# keyboard.net
KiCad netlist of a schematic drawn in Altium Designer
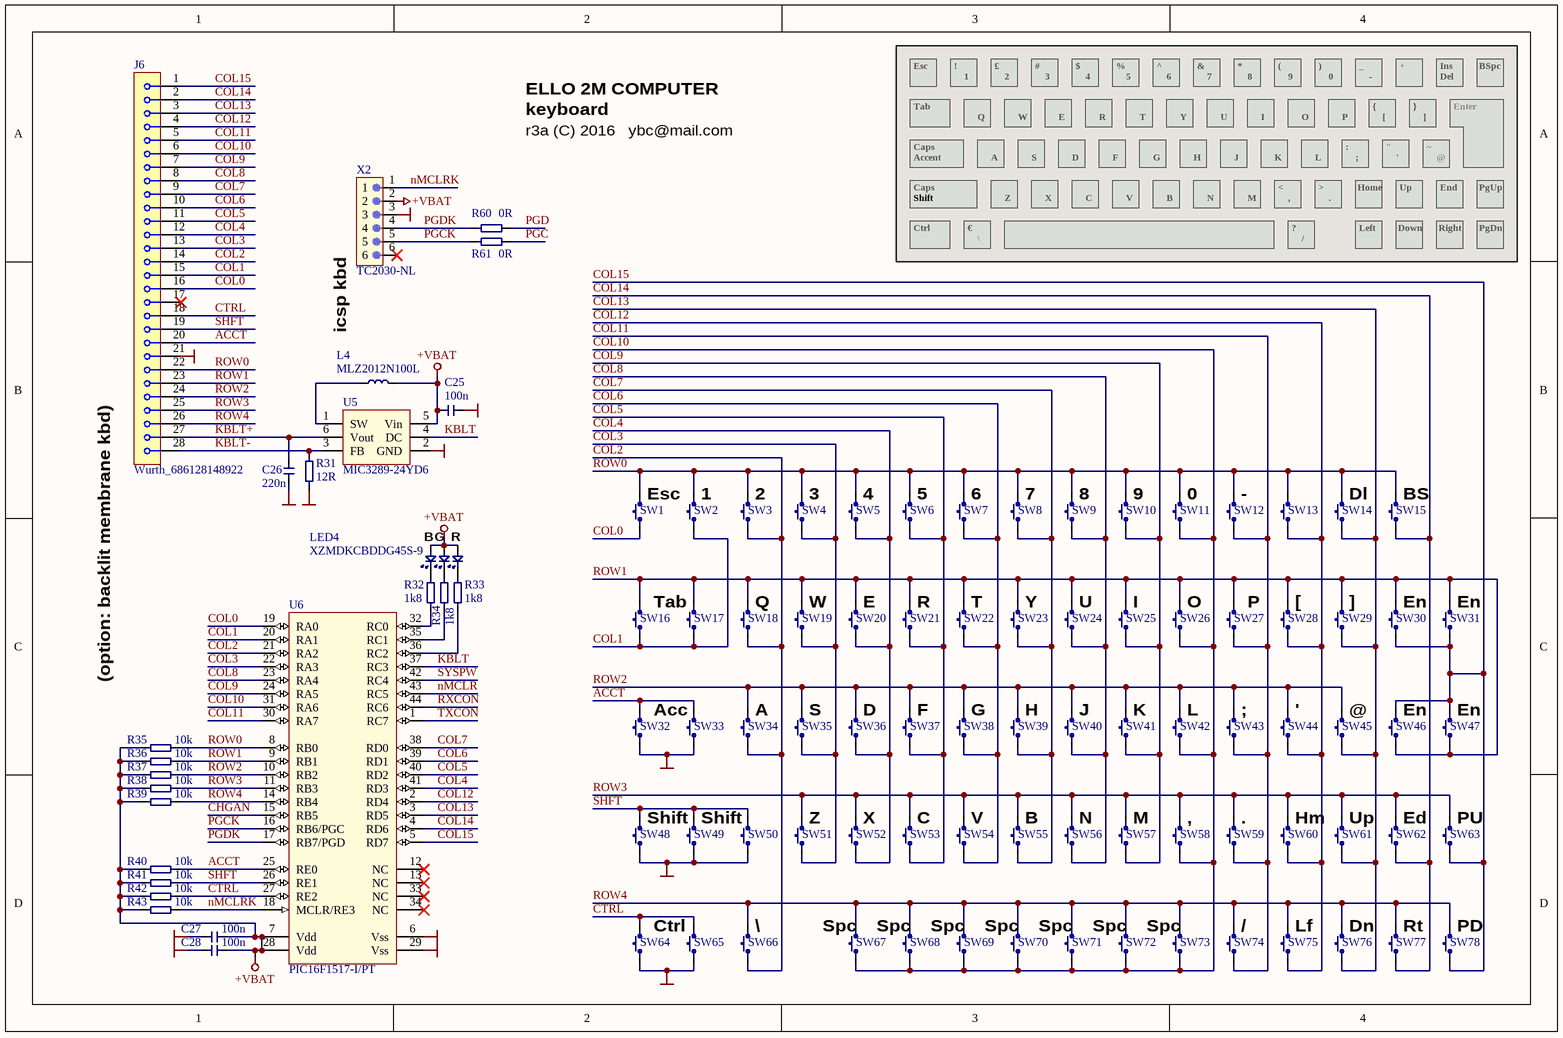
[diagram p0: keyboard.SchDoc]

(export (version "E")
  (design (tool "Eeschema 10.0.6"))
  (components
    (comp (ref "C25")
      (value "100n")
      (footprint "_0603")
      (description "Capacitor")
      (libsource (lib "Discretes") (part "Capacitor"))
    )
    (comp (ref "C26")
      (value "220n")
      (footprint "_0603")
      (description "Capacitor")
      (libsource (lib "Discretes") (part "Capacitor"))
    )
    (comp (ref "C27")
      (value "100n")
      (footprint "_0603")
      (description "Capacitor")
      (libsource (lib "Discretes") (part "Capacitor"))
    )
    (comp (ref "C28")
      (value "100n")
      (footprint "_0603")
      (description "Capacitor")
      (libsource (lib "Discretes") (part "Capacitor"))
    )
    (comp (ref "J6")
      (value "Wurth_686128148922")
      (footprint "Wurth_686128148922")
      (description "Single row, 28-way connector")
      (libsource (lib "Connectors") (part "Connector 1x28"))
    )
    (comp (ref "L4")
      (value "MLZ2012N100L")
      (footprint "_0805_IND")
      (description "Inductor")
      (libsource (lib "Discretes") (part "Inductor"))
    )
    (comp (ref "LED4")
      (value "XZMDKCBDDG45S-9")
      (footprint "LED RGB XZMDKCBDDG45S-9")
      (description "RGB Light Emitting Diode")
      (libsource (lib "Discretes") (part "LED Triple"))
    )
    (comp (ref "R31")
      (value "12R")
      (footprint "_1206")
      (description "Resistor")
      (libsource (lib "") (part "Resistor_2"))
    )
    (comp (ref "R32")
      (value "1k8")
      (footprint "_0603")
      (description "Resistor")
      (libsource (lib "") (part "Resistor_1"))
    )
    (comp (ref "R33")
      (value "1k8")
      (footprint "_0603")
      (description "Resistor")
      (libsource (lib "") (part "Resistor_1"))
    )
    (comp (ref "R34")
      (value "1k8")
      (footprint "_0603")
      (description "Resistor")
      (libsource (lib "") (part "Resistor_1"))
    )
    (comp (ref "R35")
      (value "10k")
      (footprint "_0603")
      (description "Resistor")
      (libsource (lib "Discretes") (part "Resistor"))
    )
    (comp (ref "R36")
      (value "10k")
      (footprint "_0603")
      (description "Resistor")
      (libsource (lib "Discretes") (part "Resistor"))
    )
    (comp (ref "R37")
      (value "10k")
      (footprint "_0603")
      (description "Resistor")
      (libsource (lib "Discretes") (part "Resistor"))
    )
    (comp (ref "R38")
      (value "10k")
      (footprint "_0603")
      (description "Resistor")
      (libsource (lib "Discretes") (part "Resistor"))
    )
    (comp (ref "R39")
      (value "10k")
      (footprint "_0603")
      (description "Resistor")
      (libsource (lib "Discretes") (part "Resistor"))
    )
    (comp (ref "R40")
      (value "10k")
      (footprint "_0603")
      (description "Resistor")
      (libsource (lib "Discretes") (part "Resistor"))
    )
    (comp (ref "R41")
      (value "10k")
      (footprint "_0603")
      (description "Resistor")
      (libsource (lib "Discretes") (part "Resistor"))
    )
    (comp (ref "R42")
      (value "10k")
      (footprint "_0603")
      (description "Resistor")
      (libsource (lib "Discretes") (part "Resistor"))
    )
    (comp (ref "R43")
      (value "10k")
      (footprint "_0603")
      (description "Resistor")
      (libsource (lib "Discretes") (part "Resistor"))
    )
    (comp (ref "R60")
      (value "0R")
      (footprint "_0603")
      (description "Resistor")
      (libsource (lib "") (part "Resistor_3"))
    )
    (comp (ref "R61")
      (value "0R")
      (footprint "_0603")
      (description "Resistor")
      (libsource (lib "") (part "Resistor_3"))
    )
    (comp (ref "SW1")
      (value "~")
      (footprint "Rubber Switch Pad (12mm)")
      (description "Switch, Momentary, Normal Open")
      (libsource (lib "Switches") (part "Switch MNO SPST"))
    )
    (comp (ref "SW2")
      (value "~")
      (footprint "Rubber Switch Pad (12mm)")
      (description "Switch, Momentary, Normal Open")
      (libsource (lib "Switches") (part "Switch MNO SPST"))
    )
    (comp (ref "SW3")
      (value "~")
      (footprint "Rubber Switch Pad (12mm)")
      (description "Switch, Momentary, Normal Open")
      (libsource (lib "Switches") (part "Switch MNO SPST"))
    )
    (comp (ref "SW4")
      (value "~")
      (footprint "Rubber Switch Pad (12mm)")
      (description "Switch, Momentary, Normal Open")
      (libsource (lib "Switches") (part "Switch MNO SPST"))
    )
    (comp (ref "SW5")
      (value "~")
      (footprint "Rubber Switch Pad (12mm)")
      (description "Switch, Momentary, Normal Open")
      (libsource (lib "Switches") (part "Switch MNO SPST"))
    )
    (comp (ref "SW6")
      (value "~")
      (footprint "Rubber Switch Pad (12mm)")
      (description "Switch, Momentary, Normal Open")
      (libsource (lib "Switches") (part "Switch MNO SPST"))
    )
    (comp (ref "SW7")
      (value "~")
      (footprint "Rubber Switch Pad (12mm)")
      (description "Switch, Momentary, Normal Open")
      (libsource (lib "Switches") (part "Switch MNO SPST"))
    )
    (comp (ref "SW8")
      (value "~")
      (footprint "Rubber Switch Pad (12mm)")
      (description "Switch, Momentary, Normal Open")
      (libsource (lib "Switches") (part "Switch MNO SPST"))
    )
    (comp (ref "SW9")
      (value "~")
      (footprint "Rubber Switch Pad (12mm)")
      (description "Switch, Momentary, Normal Open")
      (libsource (lib "Switches") (part "Switch MNO SPST"))
    )
    (comp (ref "SW10")
      (value "~")
      (footprint "Rubber Switch Pad (12mm)")
      (description "Switch, Momentary, Normal Open")
      (libsource (lib "Switches") (part "Switch MNO SPST"))
    )
    (comp (ref "SW11")
      (value "~")
      (footprint "Rubber Switch Pad (12mm)")
      (description "Switch, Momentary, Normal Open")
      (libsource (lib "Switches") (part "Switch MNO SPST"))
    )
    (comp (ref "SW12")
      (value "~")
      (footprint "Rubber Switch Pad (12mm)")
      (description "Switch, Momentary, Normal Open")
      (libsource (lib "Switches") (part "Switch MNO SPST"))
    )
    (comp (ref "SW13")
      (value "~")
      (footprint "Rubber Switch Pad (12mm)")
      (description "Switch, Momentary, Normal Open")
      (libsource (lib "Switches") (part "Switch MNO SPST"))
    )
    (comp (ref "SW14")
      (value "~")
      (footprint "Rubber Switch Pad (12mm)")
      (description "Switch, Momentary, Normal Open")
      (libsource (lib "Switches") (part "Switch MNO SPST"))
    )
    (comp (ref "SW15")
      (value "~")
      (footprint "Rubber Switch Pad (12mm)")
      (description "Switch, Momentary, Normal Open")
      (libsource (lib "Switches") (part "Switch MNO SPST"))
    )
    (comp (ref "SW16")
      (value "~")
      (footprint "Rubber Switch Pad (8x12mm)")
      (description "Switch, Momentary, Normal Open")
      (libsource (lib "Switches") (part "Switch MNO SPST"))
    )
    (comp (ref "SW17")
      (value "~")
      (footprint "Rubber Switch Pad (8x12mm)")
      (description "Switch, Momentary, Normal Open")
      (libsource (lib "Switches") (part "Switch MNO SPST"))
    )
    (comp (ref "SW18")
      (value "~")
      (footprint "Rubber Switch Pad (12mm)")
      (description "Switch, Momentary, Normal Open")
      (libsource (lib "Switches") (part "Switch MNO SPST"))
    )
    (comp (ref "SW19")
      (value "~")
      (footprint "Rubber Switch Pad (12mm)")
      (description "Switch, Momentary, Normal Open")
      (libsource (lib "Switches") (part "Switch MNO SPST"))
    )
    (comp (ref "SW20")
      (value "~")
      (footprint "Rubber Switch Pad (12mm)")
      (description "Switch, Momentary, Normal Open")
      (libsource (lib "Switches") (part "Switch MNO SPST"))
    )
    (comp (ref "SW21")
      (value "~")
      (footprint "Rubber Switch Pad (12mm)")
      (description "Switch, Momentary, Normal Open")
      (libsource (lib "Switches") (part "Switch MNO SPST"))
    )
    (comp (ref "SW22")
      (value "~")
      (footprint "Rubber Switch Pad (12mm)")
      (description "Switch, Momentary, Normal Open")
      (libsource (lib "Switches") (part "Switch MNO SPST"))
    )
    (comp (ref "SW23")
      (value "~")
      (footprint "Rubber Switch Pad (12mm)")
      (description "Switch, Momentary, Normal Open")
      (libsource (lib "Switches") (part "Switch MNO SPST"))
    )
    (comp (ref "SW24")
      (value "~")
      (footprint "Rubber Switch Pad (12mm)")
      (description "Switch, Momentary, Normal Open")
      (libsource (lib "Switches") (part "Switch MNO SPST"))
    )
    (comp (ref "SW25")
      (value "~")
      (footprint "Rubber Switch Pad (12mm)")
      (description "Switch, Momentary, Normal Open")
      (libsource (lib "Switches") (part "Switch MNO SPST"))
    )
    (comp (ref "SW26")
      (value "~")
      (footprint "Rubber Switch Pad (12mm)")
      (description "Switch, Momentary, Normal Open")
      (libsource (lib "Switches") (part "Switch MNO SPST"))
    )
    (comp (ref "SW27")
      (value "~")
      (footprint "Rubber Switch Pad (12mm)")
      (description "Switch, Momentary, Normal Open")
      (libsource (lib "Switches") (part "Switch MNO SPST"))
    )
    (comp (ref "SW28")
      (value "~")
      (footprint "Rubber Switch Pad (12mm)")
      (description "Switch, Momentary, Normal Open")
      (libsource (lib "Switches") (part "Switch MNO SPST"))
    )
    (comp (ref "SW29")
      (value "~")
      (footprint "Rubber Switch Pad (12mm)")
      (description "Switch, Momentary, Normal Open")
      (libsource (lib "Switches") (part "Switch MNO SPST"))
    )
    (comp (ref "SW30")
      (value "~")
      (footprint "Rubber Switch Pad (10x16mm)")
      (description "Switch, Momentary, Normal Open")
      (libsource (lib "Switches") (part "Switch MNO SPST"))
    )
    (comp (ref "SW31")
      (value "~")
      (footprint "Rubber Switch Pad (12x16mm)")
      (description "Switch, Momentary, Normal Open")
      (libsource (lib "Switches") (part "Switch MNO SPST"))
    )
    (comp (ref "SW32")
      (value "~")
      (footprint "Rubber Switch Pad (12mm)")
      (description "Switch, Momentary, Normal Open")
      (libsource (lib "Switches") (part "Switch MNO SPST"))
    )
    (comp (ref "SW33")
      (value "~")
      (footprint "Rubber Switch Pad (10x12mm)")
      (description "Switch, Momentary, Normal Open")
      (libsource (lib "Switches") (part "Switch MNO SPST"))
    )
    (comp (ref "SW34")
      (value "~")
      (footprint "Rubber Switch Pad (12mm)")
      (description "Switch, Momentary, Normal Open")
      (libsource (lib "Switches") (part "Switch MNO SPST"))
    )
    (comp (ref "SW35")
      (value "~")
      (footprint "Rubber Switch Pad (12mm)")
      (description "Switch, Momentary, Normal Open")
      (libsource (lib "Switches") (part "Switch MNO SPST"))
    )
    (comp (ref "SW36")
      (value "~")
      (footprint "Rubber Switch Pad (12mm)")
      (description "Switch, Momentary, Normal Open")
      (libsource (lib "Switches") (part "Switch MNO SPST"))
    )
    (comp (ref "SW37")
      (value "~")
      (footprint "Rubber Switch Pad (12mm)")
      (description "Switch, Momentary, Normal Open")
      (libsource (lib "Switches") (part "Switch MNO SPST"))
    )
    (comp (ref "SW38")
      (value "~")
      (footprint "Rubber Switch Pad (12mm)")
      (description "Switch, Momentary, Normal Open")
      (libsource (lib "Switches") (part "Switch MNO SPST"))
    )
    (comp (ref "SW39")
      (value "~")
      (footprint "Rubber Switch Pad (12mm)")
      (description "Switch, Momentary, Normal Open")
      (libsource (lib "Switches") (part "Switch MNO SPST"))
    )
    (comp (ref "SW40")
      (value "~")
      (footprint "Rubber Switch Pad (12mm)")
      (description "Switch, Momentary, Normal Open")
      (libsource (lib "Switches") (part "Switch MNO SPST"))
    )
    (comp (ref "SW41")
      (value "~")
      (footprint "Rubber Switch Pad (12mm)")
      (description "Switch, Momentary, Normal Open")
      (libsource (lib "Switches") (part "Switch MNO SPST"))
    )
    (comp (ref "SW42")
      (value "~")
      (footprint "Rubber Switch Pad (12mm)")
      (description "Switch, Momentary, Normal Open")
      (libsource (lib "Switches") (part "Switch MNO SPST"))
    )
    (comp (ref "SW43")
      (value "~")
      (footprint "Rubber Switch Pad (12mm)")
      (description "Switch, Momentary, Normal Open")
      (libsource (lib "Switches") (part "Switch MNO SPST"))
    )
    (comp (ref "SW44")
      (value "~")
      (footprint "Rubber Switch Pad (12mm)")
      (description "Switch, Momentary, Normal Open")
      (libsource (lib "Switches") (part "Switch MNO SPST"))
    )
    (comp (ref "SW45")
      (value "~")
      (footprint "Rubber Switch Pad (12mm)")
      (description "Switch, Momentary, Normal Open")
      (libsource (lib "Switches") (part "Switch MNO SPST"))
    )
    (comp (ref "SW46")
      (value "~")
      (footprint "Rubber Switch Pad (8x16mm)")
      (description "Switch, Momentary, Normal Open")
      (libsource (lib "Switches") (part "Switch MNO SPST"))
    )
    (comp (ref "SW47")
      (value "~")
      (footprint "Rubber Switch Pad (8x16mm)")
      (description "Switch, Momentary, Normal Open")
      (libsource (lib "Switches") (part "Switch MNO SPST"))
    )
    (comp (ref "SW48")
      (value "~")
      (footprint "Rubber Switch Pad (8x12mm)")
      (description "Switch, Momentary, Normal Open")
      (libsource (lib "Switches") (part "Switch MNO SPST"))
    )
    (comp (ref "SW49")
      (value "~")
      (footprint "Rubber Switch Pad (10X12mm)")
      (description "Switch, Momentary, Normal Open")
      (libsource (lib "Switches") (part "Switch MNO SPST"))
    )
    (comp (ref "SW50")
      (value "~")
      (footprint "Rubber Switch Pad (8x12mm)")
      (description "Switch, Momentary, Normal Open")
      (libsource (lib "Switches") (part "Switch MNO SPST"))
    )
    (comp (ref "SW51")
      (value "~")
      (footprint "Rubber Switch Pad (12mm)")
      (description "Switch, Momentary, Normal Open")
      (libsource (lib "Switches") (part "Switch MNO SPST"))
    )
    (comp (ref "SW52")
      (value "~")
      (footprint "Rubber Switch Pad (12mm)")
      (description "Switch, Momentary, Normal Open")
      (libsource (lib "Switches") (part "Switch MNO SPST"))
    )
    (comp (ref "SW53")
      (value "~")
      (footprint "Rubber Switch Pad (12mm)")
      (description "Switch, Momentary, Normal Open")
      (libsource (lib "Switches") (part "Switch MNO SPST"))
    )
    (comp (ref "SW54")
      (value "~")
      (footprint "Rubber Switch Pad (12mm)")
      (description "Switch, Momentary, Normal Open")
      (libsource (lib "Switches") (part "Switch MNO SPST"))
    )
    (comp (ref "SW55")
      (value "~")
      (footprint "Rubber Switch Pad (12mm)")
      (description "Switch, Momentary, Normal Open")
      (libsource (lib "Switches") (part "Switch MNO SPST"))
    )
    (comp (ref "SW56")
      (value "~")
      (footprint "Rubber Switch Pad (12mm)")
      (description "Switch, Momentary, Normal Open")
      (libsource (lib "Switches") (part "Switch MNO SPST"))
    )
    (comp (ref "SW57")
      (value "~")
      (footprint "Rubber Switch Pad (12mm)")
      (description "Switch, Momentary, Normal Open")
      (libsource (lib "Switches") (part "Switch MNO SPST"))
    )
    (comp (ref "SW58")
      (value "~")
      (footprint "Rubber Switch Pad (12mm)")
      (description "Switch, Momentary, Normal Open")
      (libsource (lib "Switches") (part "Switch MNO SPST"))
    )
    (comp (ref "SW59")
      (value "~")
      (footprint "Rubber Switch Pad (12mm)")
      (description "Switch, Momentary, Normal Open")
      (libsource (lib "Switches") (part "Switch MNO SPST"))
    )
    (comp (ref "SW60")
      (value "~")
      (footprint "Rubber Switch Pad (12mm)")
      (description "Switch, Momentary, Normal Open")
      (libsource (lib "Switches") (part "Switch MNO SPST"))
    )
    (comp (ref "SW61")
      (value "~")
      (footprint "Rubber Switch Pad (12mm)")
      (description "Switch, Momentary, Normal Open")
      (libsource (lib "Switches") (part "Switch MNO SPST"))
    )
    (comp (ref "SW62")
      (value "~")
      (footprint "Rubber Switch Pad (12mm)")
      (description "Switch, Momentary, Normal Open")
      (libsource (lib "Switches") (part "Switch MNO SPST"))
    )
    (comp (ref "SW63")
      (value "~")
      (footprint "Rubber Switch Pad (12mm)")
      (description "Switch, Momentary, Normal Open")
      (libsource (lib "Switches") (part "Switch MNO SPST"))
    )
    (comp (ref "SW64")
      (value "~")
      (footprint "Rubber Switch Pad (8x12mm)")
      (description "Switch, Momentary, Normal Open")
      (libsource (lib "Switches") (part "Switch MNO SPST"))
    )
    (comp (ref "SW65")
      (value "~")
      (footprint "Rubber Switch Pad (8x12mm)")
      (description "Switch, Momentary, Normal Open")
      (libsource (lib "Switches") (part "Switch MNO SPST"))
    )
    (comp (ref "SW66")
      (value "~")
      (footprint "Rubber Switch Pad (12mm)")
      (description "Switch, Momentary, Normal Open")
      (libsource (lib "Switches") (part "Switch MNO SPST"))
    )
    (comp (ref "SW67")
      (value "~")
      (footprint "Rubber Switch Pad (14x12mm)")
      (description "Switch, Momentary, Normal Open")
      (libsource (lib "Switches") (part "Switch MNO SPST"))
    )
    (comp (ref "SW68")
      (value "~")
      (footprint "Rubber Switch Pad (16x12mm)")
      (description "Switch, Momentary, Normal Open")
      (libsource (lib "Switches") (part "Switch MNO SPST"))
    )
    (comp (ref "SW69")
      (value "~")
      (footprint "Rubber Switch Pad (16x12mm)")
      (description "Switch, Momentary, Normal Open")
      (libsource (lib "Switches") (part "Switch MNO SPST"))
    )
    (comp (ref "SW70")
      (value "~")
      (footprint "Rubber Switch Pad (16x12mm)")
      (description "Switch, Momentary, Normal Open")
      (libsource (lib "Switches") (part "Switch MNO SPST"))
    )
    (comp (ref "SW71")
      (value "~")
      (footprint "Rubber Switch Pad (16x12mm)")
      (description "Switch, Momentary, Normal Open")
      (libsource (lib "Switches") (part "Switch MNO SPST"))
    )
    (comp (ref "SW72")
      (value "~")
      (footprint "Rubber Switch Pad (16x12mm)")
      (description "Switch, Momentary, Normal Open")
      (libsource (lib "Switches") (part "Switch MNO SPST"))
    )
    (comp (ref "SW73")
      (value "~")
      (footprint "Rubber Switch Pad (14x12mm)")
      (description "Switch, Momentary, Normal Open")
      (libsource (lib "Switches") (part "Switch MNO SPST"))
    )
    (comp (ref "SW74")
      (value "~")
      (footprint "Rubber Switch Pad (12mm)")
      (description "Switch, Momentary, Normal Open")
      (libsource (lib "Switches") (part "Switch MNO SPST"))
    )
    (comp (ref "SW75")
      (value "~")
      (footprint "Rubber Switch Pad (12mm)")
      (description "Switch, Momentary, Normal Open")
      (libsource (lib "Switches") (part "Switch MNO SPST"))
    )
    (comp (ref "SW76")
      (value "~")
      (footprint "Rubber Switch Pad (12mm)")
      (description "Switch, Momentary, Normal Open")
      (libsource (lib "Switches") (part "Switch MNO SPST"))
    )
    (comp (ref "SW77")
      (value "~")
      (footprint "Rubber Switch Pad (12mm)")
      (description "Switch, Momentary, Normal Open")
      (libsource (lib "Switches") (part "Switch MNO SPST"))
    )
    (comp (ref "SW78")
      (value "~")
      (footprint "Rubber Switch Pad (12mm)")
      (description "Switch, Momentary, Normal Open")
      (libsource (lib "Switches") (part "Switch MNO SPST"))
    )
    (comp (ref "U5")
      (value "MIC3289-24YD6")
      (footprint "SOT23-6")
      (description "White LED Driver")
      (fields (field (name "MANUFACTURER") "Microchip (Micrel)"))
      (libsource (lib "IC Drivers and Switches") (part "MIC3289 (SOT26)"))
    )
    (comp (ref "U6")
      (value "PIC16F1517-I/PT")
      (footprint "QFP80P1200X1200X120-44N")
      (description "44-Pin Flash Microcontrollers with nanoWatt XLP Technology")
      (fields (field (name "MANUFACTURER") "Microchip"))
      (libsource (lib "IC Microcontrollers and Processors") (part "PIC16(L)F1904/07"))
    )
    (comp (ref "X2")
      (value "TC2030-NL")
      (footprint "TC2030-NL")
      (description "TC2030 nails connector")
      (fields (field (name "MANUFACTURER") "www.tag-connect.com"))
      (libsource (lib "Connectors") (part "TC2030"))
    )
  )
  (nets
    (net (code "1") (name "+VBAT") (class "Default")
      (node (ref "C25") (pin "1") (pintype "passive"))
      (node (ref "C27") (pin "2") (pintype "passive"))
      (node (ref "C28") (pin "2") (pintype "passive"))
      (node (ref "L4") (pin "2") (pintype "passive"))
      (node (ref "LED4") (pin "2") (pintype "passive"))
      (node (ref "R35") (pin "1") (pintype "passive"))
      (node (ref "R36") (pin "1") (pintype "passive"))
      (node (ref "R37") (pin "1") (pintype "passive"))
      (node (ref "R38") (pin "1") (pintype "passive"))
      (node (ref "R39") (pin "1") (pintype "passive"))
      (node (ref "R40") (pin "1") (pintype "passive"))
      (node (ref "R41") (pin "1") (pintype "passive"))
      (node (ref "R42") (pin "1") (pintype "passive"))
      (node (ref "R43") (pin "1") (pintype "passive"))
      (node (ref "U5") (pin "5") (pinfunction "Vin_5") (pintype "power_in"))
      (node (ref "U6") (pin "28") (pinfunction "Vdd_28") (pintype "power_in"))
      (node (ref "U6") (pin "7") (pinfunction "Vdd_7") (pintype "power_in"))
      (node (ref "X2") (pin "2") (pinfunction "2_2") (pintype "passive"))
    )
    (net (code "2") (name "/ACCT") (class "Default")
      (node (ref "J6") (pin "20") (pinfunction "20_20") (pintype "passive"))
      (node (ref "R40") (pin "2") (pintype "passive"))
      (node (ref "SW32") (pin "2") (pintype "passive"))
      (node (ref "SW33") (pin "2") (pintype "passive"))
      (node (ref "U6") (pin "25") (pinfunction "RE0_25") (pintype "bidirectional"))
    )
    (net (code "3") (name "/CHGAN") (class "Default")
      (node (ref "U6") (pin "15") (pinfunction "RB5_15") (pintype "bidirectional"))
    )
    (net (code "4") (name "/COL0") (class "Default")
      (node (ref "J6") (pin "16") (pinfunction "16_16") (pintype "passive"))
      (node (ref "SW1") (pin "1") (pintype "passive"))
      (node (ref "U6") (pin "19") (pinfunction "RA0_19") (pintype "bidirectional"))
    )
    (net (code "5") (name "/COL1") (class "Default")
      (node (ref "J6") (pin "15") (pinfunction "15_15") (pintype "passive"))
      (node (ref "SW16") (pin "1") (pintype "passive"))
      (node (ref "SW17") (pin "1") (pintype "passive"))
      (node (ref "SW2") (pin "1") (pintype "passive"))
      (node (ref "U6") (pin "20") (pinfunction "RA1_20") (pintype "bidirectional"))
    )
    (net (code "6") (name "/COL2") (class "Default")
      (node (ref "J6") (pin "14") (pinfunction "14_14") (pintype "passive"))
      (node (ref "SW18") (pin "1") (pintype "passive"))
      (node (ref "SW3") (pin "1") (pintype "passive"))
      (node (ref "SW34") (pin "1") (pintype "passive"))
      (node (ref "SW66") (pin "1") (pintype "passive"))
      (node (ref "U6") (pin "21") (pinfunction "RA2_21") (pintype "bidirectional"))
    )
    (net (code "7") (name "/COL3") (class "Default")
      (node (ref "J6") (pin "13") (pinfunction "13_13") (pintype "passive"))
      (node (ref "SW19") (pin "1") (pintype "passive"))
      (node (ref "SW35") (pin "1") (pintype "passive"))
      (node (ref "SW4") (pin "1") (pintype "passive"))
      (node (ref "SW51") (pin "1") (pintype "passive"))
      (node (ref "U6") (pin "22") (pinfunction "RA3_22") (pintype "bidirectional"))
    )
    (net (code "8") (name "/COL4") (class "Default")
      (node (ref "J6") (pin "12") (pinfunction "12_12") (pintype "passive"))
      (node (ref "SW20") (pin "1") (pintype "passive"))
      (node (ref "SW36") (pin "1") (pintype "passive"))
      (node (ref "SW5") (pin "1") (pintype "passive"))
      (node (ref "SW52") (pin "1") (pintype "passive"))
      (node (ref "U6") (pin "41") (pinfunction "RD3_41") (pintype "bidirectional"))
    )
    (net (code "9") (name "/COL5") (class "Default")
      (node (ref "J6") (pin "11") (pinfunction "11_11") (pintype "passive"))
      (node (ref "SW21") (pin "1") (pintype "passive"))
      (node (ref "SW37") (pin "1") (pintype "passive"))
      (node (ref "SW53") (pin "1") (pintype "passive"))
      (node (ref "SW6") (pin "1") (pintype "passive"))
      (node (ref "U6") (pin "40") (pinfunction "RD2_40") (pintype "bidirectional"))
    )
    (net (code "10") (name "/COL6") (class "Default")
      (node (ref "J6") (pin "10") (pinfunction "10_10") (pintype "passive"))
      (node (ref "SW22") (pin "1") (pintype "passive"))
      (node (ref "SW38") (pin "1") (pintype "passive"))
      (node (ref "SW54") (pin "1") (pintype "passive"))
      (node (ref "SW7") (pin "1") (pintype "passive"))
      (node (ref "U6") (pin "39") (pinfunction "RD1_39") (pintype "bidirectional"))
    )
    (net (code "11") (name "/COL7") (class "Default")
      (node (ref "J6") (pin "9") (pinfunction "9_9") (pintype "passive"))
      (node (ref "SW23") (pin "1") (pintype "passive"))
      (node (ref "SW39") (pin "1") (pintype "passive"))
      (node (ref "SW55") (pin "1") (pintype "passive"))
      (node (ref "SW8") (pin "1") (pintype "passive"))
      (node (ref "U6") (pin "38") (pinfunction "RD0_38") (pintype "bidirectional"))
    )
    (net (code "12") (name "/COL8") (class "Default")
      (node (ref "J6") (pin "8") (pinfunction "8_8") (pintype "passive"))
      (node (ref "SW24") (pin "1") (pintype "passive"))
      (node (ref "SW40") (pin "1") (pintype "passive"))
      (node (ref "SW56") (pin "1") (pintype "passive"))
      (node (ref "SW9") (pin "1") (pintype "passive"))
      (node (ref "U6") (pin "23") (pinfunction "RA4_23") (pintype "bidirectional"))
    )
    (net (code "13") (name "/COL9") (class "Default")
      (node (ref "J6") (pin "7") (pinfunction "7_7") (pintype "passive"))
      (node (ref "SW10") (pin "1") (pintype "passive"))
      (node (ref "SW25") (pin "1") (pintype "passive"))
      (node (ref "SW41") (pin "1") (pintype "passive"))
      (node (ref "SW57") (pin "1") (pintype "passive"))
      (node (ref "U6") (pin "24") (pinfunction "RA5_24") (pintype "bidirectional"))
    )
    (net (code "14") (name "/COL10") (class "Default")
      (node (ref "J6") (pin "6") (pinfunction "6_6") (pintype "passive"))
      (node (ref "SW11") (pin "1") (pintype "passive"))
      (node (ref "SW26") (pin "1") (pintype "passive"))
      (node (ref "SW42") (pin "1") (pintype "passive"))
      (node (ref "SW58") (pin "1") (pintype "passive"))
      (node (ref "SW67") (pin "1") (pintype "passive"))
      (node (ref "SW68") (pin "1") (pintype "passive"))
      (node (ref "SW69") (pin "1") (pintype "passive"))
      (node (ref "SW70") (pin "1") (pintype "passive"))
      (node (ref "SW71") (pin "1") (pintype "passive"))
      (node (ref "SW72") (pin "1") (pintype "passive"))
      (node (ref "SW73") (pin "1") (pintype "passive"))
      (node (ref "U6") (pin "31") (pinfunction "RA6_31") (pintype "bidirectional"))
    )
    (net (code "15") (name "/COL11") (class "Default")
      (node (ref "J6") (pin "5") (pinfunction "5_5") (pintype "passive"))
      (node (ref "SW12") (pin "1") (pintype "passive"))
      (node (ref "SW27") (pin "1") (pintype "passive"))
      (node (ref "SW43") (pin "1") (pintype "passive"))
      (node (ref "SW59") (pin "1") (pintype "passive"))
      (node (ref "SW74") (pin "1") (pintype "passive"))
      (node (ref "U6") (pin "30") (pinfunction "RA7_30") (pintype "bidirectional"))
    )
    (net (code "16") (name "/COL12") (class "Default")
      (node (ref "J6") (pin "4") (pinfunction "4_4") (pintype "passive"))
      (node (ref "SW13") (pin "1") (pintype "passive"))
      (node (ref "SW28") (pin "1") (pintype "passive"))
      (node (ref "SW44") (pin "1") (pintype "passive"))
      (node (ref "SW60") (pin "1") (pintype "passive"))
      (node (ref "SW75") (pin "1") (pintype "passive"))
      (node (ref "U6") (pin "2") (pinfunction "RD4_2") (pintype "bidirectional"))
    )
    (net (code "17") (name "/COL13") (class "Default")
      (node (ref "J6") (pin "3") (pinfunction "3_3") (pintype "passive"))
      (node (ref "SW14") (pin "1") (pintype "passive"))
      (node (ref "SW29") (pin "1") (pintype "passive"))
      (node (ref "SW45") (pin "1") (pintype "passive"))
      (node (ref "SW61") (pin "1") (pintype "passive"))
      (node (ref "SW76") (pin "1") (pintype "passive"))
      (node (ref "U6") (pin "3") (pinfunction "RD5_3") (pintype "bidirectional"))
    )
    (net (code "18") (name "/COL14") (class "Default")
      (node (ref "J6") (pin "2") (pinfunction "2_2") (pintype "passive"))
      (node (ref "SW15") (pin "1") (pintype "passive"))
      (node (ref "SW62") (pin "1") (pintype "passive"))
      (node (ref "SW77") (pin "1") (pintype "passive"))
      (node (ref "U6") (pin "4") (pinfunction "RD6_4") (pintype "bidirectional"))
    )
    (net (code "19") (name "/COL15") (class "Default")
      (node (ref "J6") (pin "1") (pinfunction "1_1") (pintype "passive"))
      (node (ref "SW30") (pin "1") (pintype "passive"))
      (node (ref "SW31") (pin "1") (pintype "passive"))
      (node (ref "SW46") (pin "2") (pintype "passive"))
      (node (ref "SW47") (pin "2") (pintype "passive"))
      (node (ref "SW63") (pin "1") (pintype "passive"))
      (node (ref "SW78") (pin "1") (pintype "passive"))
      (node (ref "U6") (pin "5") (pinfunction "RD7_5") (pintype "bidirectional"))
    )
    (net (code "20") (name "/CTRL") (class "Default")
      (node (ref "J6") (pin "18") (pinfunction "18_18") (pintype "passive"))
      (node (ref "R42") (pin "2") (pintype "passive"))
      (node (ref "SW64") (pin "2") (pintype "passive"))
      (node (ref "SW65") (pin "2") (pintype "passive"))
      (node (ref "U6") (pin "27") (pinfunction "RE2_27") (pintype "bidirectional"))
    )
    (net (code "21") (name "/KBLT") (class "Default")
      (node (ref "U5") (pin "4") (pinfunction "DC_4") (pintype "passive"))
      (node (ref "U6") (pin "37") (pinfunction "RC3_37") (pintype "bidirectional"))
    )
    (net (code "22") (name "/KBLT+") (class "Default")
      (node (ref "C26") (pin "2") (pintype "passive"))
      (node (ref "J6") (pin "27") (pinfunction "27_27") (pintype "passive"))
      (node (ref "U5") (pin "6") (pinfunction "Vout_6") (pintype "passive"))
    )
    (net (code "23") (name "/KBLT-") (class "Default")
      (node (ref "J6") (pin "28") (pinfunction "28_28") (pintype "passive"))
      (node (ref "R31") (pin "1") (pintype "passive"))
      (node (ref "U5") (pin "3") (pinfunction "FB_3") (pintype "passive"))
    )
    (net (code "24") (name "/PGC") (class "Default") (node (ref "R61") (pin "1") (pintype "passive")))
    (net (code "25") (name "/PGCK") (class "Default")
      (node (ref "R61") (pin "2") (pintype "passive"))
      (node (ref "U6") (pin "16") (pinfunction "RB6/PGC_16") (pintype "bidirectional"))
      (node (ref "X2") (pin "5") (pinfunction "5_5") (pintype "passive"))
    )
    (net (code "26") (name "/PGD") (class "Default") (node (ref "R60") (pin "1") (pintype "passive")))
    (net (code "27") (name "/PGDK") (class "Default")
      (node (ref "R60") (pin "2") (pintype "passive"))
      (node (ref "U6") (pin "17") (pinfunction "RB7/PGD_17") (pintype "bidirectional"))
      (node (ref "X2") (pin "4") (pinfunction "4_4") (pintype "passive"))
    )
    (net (code "28") (name "/ROW0") (class "Default")
      (node (ref "J6") (pin "22") (pinfunction "22_22") (pintype "passive"))
      (node (ref "R35") (pin "2") (pintype "passive"))
      (node (ref "SW1") (pin "2") (pintype "passive"))
      (node (ref "SW10") (pin "2") (pintype "passive"))
      (node (ref "SW11") (pin "2") (pintype "passive"))
      (node (ref "SW12") (pin "2") (pintype "passive"))
      (node (ref "SW13") (pin "2") (pintype "passive"))
      (node (ref "SW14") (pin "2") (pintype "passive"))
      (node (ref "SW15") (pin "2") (pintype "passive"))
      (node (ref "SW2") (pin "2") (pintype "passive"))
      (node (ref "SW3") (pin "2") (pintype "passive"))
      (node (ref "SW4") (pin "2") (pintype "passive"))
      (node (ref "SW5") (pin "2") (pintype "passive"))
      (node (ref "SW6") (pin "2") (pintype "passive"))
      (node (ref "SW7") (pin "2") (pintype "passive"))
      (node (ref "SW8") (pin "2") (pintype "passive"))
      (node (ref "SW9") (pin "2") (pintype "passive"))
      (node (ref "U6") (pin "8") (pinfunction "RB0_8") (pintype "bidirectional"))
    )
    (net (code "29") (name "/ROW1") (class "Default")
      (node (ref "J6") (pin "23") (pinfunction "23_23") (pintype "passive"))
      (node (ref "R36") (pin "2") (pintype "passive"))
      (node (ref "SW16") (pin "2") (pintype "passive"))
      (node (ref "SW17") (pin "2") (pintype "passive"))
      (node (ref "SW18") (pin "2") (pintype "passive"))
      (node (ref "SW19") (pin "2") (pintype "passive"))
      (node (ref "SW20") (pin "2") (pintype "passive"))
      (node (ref "SW21") (pin "2") (pintype "passive"))
      (node (ref "SW22") (pin "2") (pintype "passive"))
      (node (ref "SW23") (pin "2") (pintype "passive"))
      (node (ref "SW24") (pin "2") (pintype "passive"))
      (node (ref "SW25") (pin "2") (pintype "passive"))
      (node (ref "SW26") (pin "2") (pintype "passive"))
      (node (ref "SW27") (pin "2") (pintype "passive"))
      (node (ref "SW28") (pin "2") (pintype "passive"))
      (node (ref "SW29") (pin "2") (pintype "passive"))
      (node (ref "SW30") (pin "2") (pintype "passive"))
      (node (ref "SW31") (pin "2") (pintype "passive"))
      (node (ref "SW46") (pin "1") (pintype "passive"))
      (node (ref "SW47") (pin "1") (pintype "passive"))
      (node (ref "U6") (pin "9") (pinfunction "RB1_9") (pintype "bidirectional"))
    )
    (net (code "30") (name "/ROW2") (class "Default")
      (node (ref "J6") (pin "24") (pinfunction "24_24") (pintype "passive"))
      (node (ref "R37") (pin "2") (pintype "passive"))
      (node (ref "SW34") (pin "2") (pintype "passive"))
      (node (ref "SW35") (pin "2") (pintype "passive"))
      (node (ref "SW36") (pin "2") (pintype "passive"))
      (node (ref "SW37") (pin "2") (pintype "passive"))
      (node (ref "SW38") (pin "2") (pintype "passive"))
      (node (ref "SW39") (pin "2") (pintype "passive"))
      (node (ref "SW40") (pin "2") (pintype "passive"))
      (node (ref "SW41") (pin "2") (pintype "passive"))
      (node (ref "SW42") (pin "2") (pintype "passive"))
      (node (ref "SW43") (pin "2") (pintype "passive"))
      (node (ref "SW44") (pin "2") (pintype "passive"))
      (node (ref "SW45") (pin "2") (pintype "passive"))
      (node (ref "U6") (pin "10") (pinfunction "RB2_10") (pintype "bidirectional"))
    )
    (net (code "31") (name "/ROW3") (class "Default")
      (node (ref "J6") (pin "25") (pinfunction "25_25") (pintype "passive"))
      (node (ref "R38") (pin "2") (pintype "passive"))
      (node (ref "SW51") (pin "2") (pintype "passive"))
      (node (ref "SW52") (pin "2") (pintype "passive"))
      (node (ref "SW53") (pin "2") (pintype "passive"))
      (node (ref "SW54") (pin "2") (pintype "passive"))
      (node (ref "SW55") (pin "2") (pintype "passive"))
      (node (ref "SW56") (pin "2") (pintype "passive"))
      (node (ref "SW57") (pin "2") (pintype "passive"))
      (node (ref "SW58") (pin "2") (pintype "passive"))
      (node (ref "SW59") (pin "2") (pintype "passive"))
      (node (ref "SW60") (pin "2") (pintype "passive"))
      (node (ref "SW61") (pin "2") (pintype "passive"))
      (node (ref "SW62") (pin "2") (pintype "passive"))
      (node (ref "SW63") (pin "2") (pintype "passive"))
      (node (ref "U6") (pin "11") (pinfunction "RB3_11") (pintype "bidirectional"))
    )
    (net (code "32") (name "/ROW4") (class "Default")
      (node (ref "J6") (pin "26") (pinfunction "26_26") (pintype "passive"))
      (node (ref "R39") (pin "2") (pintype "passive"))
      (node (ref "SW66") (pin "2") (pintype "passive"))
      (node (ref "SW67") (pin "2") (pintype "passive"))
      (node (ref "SW68") (pin "2") (pintype "passive"))
      (node (ref "SW69") (pin "2") (pintype "passive"))
      (node (ref "SW70") (pin "2") (pintype "passive"))
      (node (ref "SW71") (pin "2") (pintype "passive"))
      (node (ref "SW72") (pin "2") (pintype "passive"))
      (node (ref "SW73") (pin "2") (pintype "passive"))
      (node (ref "SW74") (pin "2") (pintype "passive"))
      (node (ref "SW75") (pin "2") (pintype "passive"))
      (node (ref "SW76") (pin "2") (pintype "passive"))
      (node (ref "SW77") (pin "2") (pintype "passive"))
      (node (ref "SW78") (pin "2") (pintype "passive"))
      (node (ref "U6") (pin "14") (pinfunction "RB4_14") (pintype "bidirectional"))
    )
    (net (code "33") (name "/RXCON") (class "Default")
      (node (ref "U6") (pin "44") (pinfunction "RC6_44") (pintype "bidirectional"))
    )
    (net (code "34") (name "/SHFT") (class "Default")
      (node (ref "J6") (pin "19") (pinfunction "19_19") (pintype "passive"))
      (node (ref "R41") (pin "2") (pintype "passive"))
      (node (ref "SW48") (pin "2") (pintype "passive"))
      (node (ref "SW49") (pin "2") (pintype "passive"))
      (node (ref "SW50") (pin "2") (pintype "passive"))
      (node (ref "U6") (pin "26") (pinfunction "RE1_26") (pintype "bidirectional"))
    )
    (net (code "35") (name "/SYSPW") (class "Default")
      (node (ref "U6") (pin "42") (pinfunction "RC4_42") (pintype "bidirectional"))
    )
    (net (code "36") (name "/TXCON") (class "Default")
      (node (ref "U6") (pin "1") (pinfunction "RC7_1") (pintype "bidirectional"))
    )
    (net (code "37") (name "/nMCLR") (class "Default")
      (node (ref "U6") (pin "43") (pinfunction "RC5_43") (pintype "bidirectional"))
    )
    (net (code "38") (name "/nMCLRK") (class "Default")
      (node (ref "R43") (pin "2") (pintype "passive"))
      (node (ref "U6") (pin "18") (pinfunction "MCLR/RE3_18") (pintype "input"))
      (node (ref "X2") (pin "1") (pinfunction "1_1") (pintype "passive"))
    )
    (net (code "39") (name "GND") (class "Default")
      (node (ref "C25") (pin "2") (pintype "passive"))
      (node (ref "C26") (pin "1") (pintype "passive"))
      (node (ref "C27") (pin "1") (pintype "passive"))
      (node (ref "C28") (pin "1") (pintype "passive"))
      (node (ref "J6") (pin "21") (pinfunction "21_21") (pintype "passive"))
      (node (ref "R31") (pin "2") (pintype "passive"))
      (node (ref "SW32") (pin "1") (pintype "passive"))
      (node (ref "SW33") (pin "1") (pintype "passive"))
      (node (ref "SW48") (pin "1") (pintype "passive"))
      (node (ref "SW49") (pin "1") (pintype "passive"))
      (node (ref "SW50") (pin "1") (pintype "passive"))
      (node (ref "SW64") (pin "1") (pintype "passive"))
      (node (ref "SW65") (pin "1") (pintype "passive"))
      (node (ref "U5") (pin "2") (pinfunction "GND_2") (pintype "power_in"))
      (node (ref "U6") (pin "29") (pinfunction "Vss_29") (pintype "power_in"))
      (node (ref "U6") (pin "6") (pinfunction "Vss_6") (pintype "power_in"))
      (node (ref "X2") (pin "3") (pinfunction "3_3") (pintype "passive"))
    )
    (net (code "40") (name "Net-(LED4-Pad1)") (class "Default")
      (node (ref "LED4") (pin "1") (pintype "passive"))
      (node (ref "R33") (pin "2") (pintype "passive"))
    )
    (net (code "41") (name "Net-(LED4-Pad3)") (class "Default")
      (node (ref "LED4") (pin "3") (pintype "passive"))
      (node (ref "R32") (pin "2") (pintype "passive"))
    )
    (net (code "42") (name "Net-(LED4-Pad4)") (class "Default")
      (node (ref "LED4") (pin "4") (pintype "passive"))
      (node (ref "R34") (pin "2") (pintype "passive"))
    )
    (net (code "43") (name "Net-(U5-SW)") (class "Default")
      (node (ref "L4") (pin "1") (pintype "passive"))
      (node (ref "U5") (pin "1") (pinfunction "SW_1") (pintype "passive"))
    )
    (net (code "44") (name "Net-(U6-RC0)") (class "Default")
      (node (ref "R32") (pin "1") (pintype "passive"))
      (node (ref "U6") (pin "32") (pinfunction "RC0_32") (pintype "bidirectional"))
    )
    (net (code "45") (name "Net-(U6-RC1)") (class "Default")
      (node (ref "R34") (pin "1") (pintype "passive"))
      (node (ref "U6") (pin "35") (pinfunction "RC1_35") (pintype "bidirectional"))
    )
    (net (code "46") (name "Net-(U6-RC2)") (class "Default")
      (node (ref "R33") (pin "1") (pintype "passive"))
      (node (ref "U6") (pin "36") (pinfunction "RC2_36") (pintype "bidirectional"))
    )
    (net (code "47") (name "unconnected-(J6-Pad17)") (class "Default")
      (node (ref "J6") (pin "17") (pinfunction "17_17") (pintype "passive+no_connect"))
    )
    (net (code "48") (name "unconnected-(U6-NC-Pad12)") (class "Default")
      (node (ref "U6") (pin "12") (pinfunction "NC_12") (pintype "power_in+no_connect"))
    )
    (net (code "49") (name "unconnected-(U6-NC-Pad13)") (class "Default")
      (node (ref "U6") (pin "13") (pinfunction "NC_13") (pintype "power_in+no_connect"))
    )
    (net (code "50") (name "unconnected-(U6-NC-Pad33)") (class "Default")
      (node (ref "U6") (pin "33") (pinfunction "NC_33") (pintype "power_in+no_connect"))
    )
    (net (code "51") (name "unconnected-(U6-NC-Pad34)") (class "Default")
      (node (ref "U6") (pin "34") (pinfunction "NC_34") (pintype "power_in+no_connect"))
    )
    (net (code "52") (name "unconnected-(X2-Pad6)") (class "Default")
      (node (ref "X2") (pin "6") (pinfunction "6_6") (pintype "passive+no_connect"))
    )
  )
)
